# converter_in.net
KiCad netlist of a schematic drawn in EAGLE
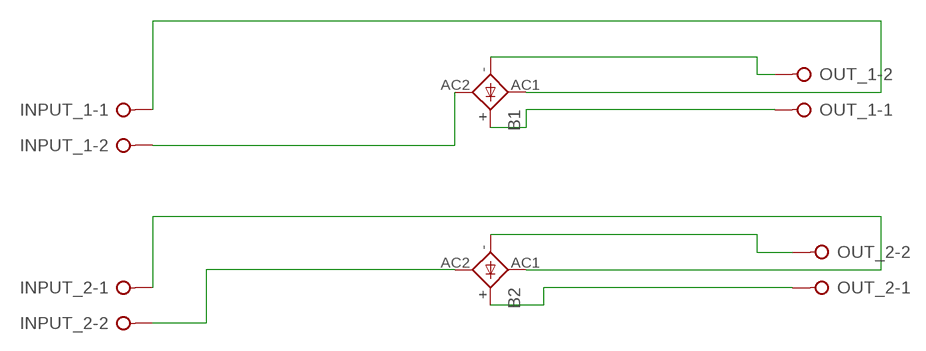
[diagram p0: schematic, sheet 1]

(export (version "E")
  (design (tool "Eeschema 10.0.6"))
  (components
    (comp (ref "B1")
      (value "2KBP")
      (footprint "eagle-import:2KBP")
      (libsource (lib "eagle-import") (part "2KBP"))
    )
    (comp (ref "B2")
      (value "2KBP")
      (footprint "eagle-import:2KBP")
      (libsource (lib "eagle-import") (part "2KBP"))
    )
    (comp (ref "INPUT_1")
      (value "W237-02P")
      (footprint "eagle-import:W237-132")
      (libsource (lib "eagle-import") (part "W237-02P"))
    )
    (comp (ref "INPUT_2")
      (value "W237-02P")
      (footprint "eagle-import:W237-132")
      (libsource (lib "eagle-import") (part "W237-02P"))
    )
    (comp (ref "OUT_1")
      (value "W237-02P")
      (footprint "eagle-import:W237-132")
      (libsource (lib "eagle-import") (part "W237-02P"))
    )
    (comp (ref "OUT_2")
      (value "W237-02P")
      (footprint "eagle-import:W237-132")
      (libsource (lib "eagle-import") (part "W237-02P"))
    )
  )
  (nets
    (net (code "1") (name "Net-(INPUT_1A-KL)") (class "Default")
      (node (ref "B1") (pin "AC1") (pinfunction "AC1_AC1") (pintype "passive"))
      (node (ref "INPUT_1") (pin "1") (pinfunction "KL_1") (pintype "passive"))
    )
    (net (code "2") (name "Net-(INPUT_1B-KL)") (class "Default")
      (node (ref "B1") (pin "AC2") (pinfunction "AC2_AC2") (pintype "passive"))
      (node (ref "INPUT_1") (pin "2") (pinfunction "KL_2") (pintype "passive"))
    )
    (net (code "3") (name "Net-(INPUT_2A-KL)") (class "Default")
      (node (ref "B2") (pin "AC1") (pinfunction "AC1_AC1") (pintype "passive"))
      (node (ref "INPUT_2") (pin "1") (pinfunction "KL_1") (pintype "passive"))
    )
    (net (code "4") (name "Net-(INPUT_2B-KL)") (class "Default")
      (node (ref "B2") (pin "AC2") (pinfunction "AC2_AC2") (pintype "passive"))
      (node (ref "INPUT_2") (pin "2") (pinfunction "KL_2") (pintype "passive"))
    )
    (net (code "5") (name "Net-(OUT_1A-KL)") (class "Default")
      (node (ref "B1") (pin "+") (pinfunction "+_+") (pintype "passive"))
      (node (ref "OUT_1") (pin "1") (pinfunction "KL_1") (pintype "passive"))
    )
    (net (code "6") (name "Net-(OUT_1B-KL)") (class "Default")
      (node (ref "B1") (pin "-") (pinfunction "-_-") (pintype "passive"))
      (node (ref "OUT_1") (pin "2") (pinfunction "KL_2") (pintype "passive"))
    )
    (net (code "7") (name "Net-(OUT_2A-KL)") (class "Default")
      (node (ref "B2") (pin "+") (pinfunction "+_+") (pintype "passive"))
      (node (ref "OUT_2") (pin "1") (pinfunction "KL_1") (pintype "passive"))
    )
    (net (code "8") (name "Net-(OUT_2B-KL)") (class "Default")
      (node (ref "B2") (pin "-") (pinfunction "-_-") (pintype "passive"))
      (node (ref "OUT_2") (pin "2") (pinfunction "KL_2") (pintype "passive"))
    )
  )
)
